# ButtonLatencyTester2.net
KiCad netlist of a schematic drawn in EAGLE
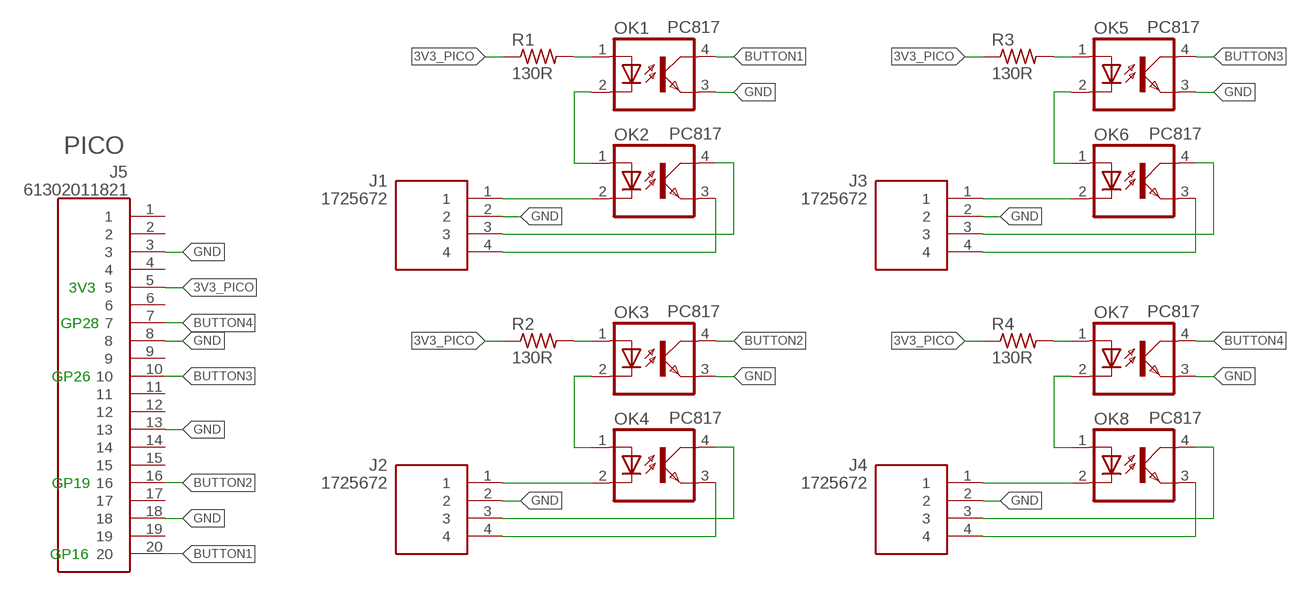
[diagram p0: schematic, sheet 1]

(export (version "E")
  (design (tool "Eeschema 10.0.6"))
  (components
    (comp (ref "J1")
      (value "1725672")
      (footprint "eagle-import:1725672-4-2.54")
      (fields (field (name "MOUSER_PART_NUMBER") "651-1725672"))
      (libsource (lib "eagle-import") (part "1725672"))
    )
    (comp (ref "J2")
      (value "1725672")
      (footprint "eagle-import:1725672-4-2.54")
      (fields (field (name "MOUSER_PART_NUMBER") "651-1725672"))
      (libsource (lib "eagle-import") (part "1725672"))
    )
    (comp (ref "J3")
      (value "1725672")
      (footprint "eagle-import:1725672-4-2.54")
      (fields (field (name "MOUSER_PART_NUMBER") "651-1725672"))
      (libsource (lib "eagle-import") (part "1725672"))
    )
    (comp (ref "J4")
      (value "1725672")
      (footprint "eagle-import:1725672-4-2.54")
      (fields (field (name "MOUSER_PART_NUMBER") "651-1725672"))
      (libsource (lib "eagle-import") (part "1725672"))
    )
    (comp (ref "J5")
      (value "61302011821")
      (footprint "eagle-import:RHDR20W60P0X254_1X20_5130X250X")
      (fields (field (name "MOUSER_PART_NUMBER") "710-61302011821"))
      (libsource (lib "eagle-import") (part "61302011821"))
    )
    (comp (ref "OK1")
      (value "PC817")
      (footprint "eagle-import:DIL04")
      (fields (field (name "MPN") "PC817X4J000F"))
      (libsource (lib "eagle-import") (part "PC817"))
    )
    (comp (ref "OK2")
      (value "PC817")
      (footprint "eagle-import:DIL04")
      (fields (field (name "MPN") "PC817X4J000F"))
      (libsource (lib "eagle-import") (part "PC817"))
    )
    (comp (ref "OK3")
      (value "PC817")
      (footprint "eagle-import:DIL04")
      (fields (field (name "MPN") "PC817X4J000F"))
      (libsource (lib "eagle-import") (part "PC817"))
    )
    (comp (ref "OK4")
      (value "PC817")
      (footprint "eagle-import:DIL04")
      (fields (field (name "MPN") "PC817X4J000F"))
      (libsource (lib "eagle-import") (part "PC817"))
    )
    (comp (ref "OK5")
      (value "PC817")
      (footprint "eagle-import:DIL04")
      (fields (field (name "MPN") "PC817X4J000F"))
      (libsource (lib "eagle-import") (part "PC817"))
    )
    (comp (ref "OK6")
      (value "PC817")
      (footprint "eagle-import:DIL04")
      (fields (field (name "MPN") "PC817X4J000F"))
      (libsource (lib "eagle-import") (part "PC817"))
    )
    (comp (ref "OK7")
      (value "PC817")
      (footprint "eagle-import:DIL04")
      (fields (field (name "MPN") "PC817X4J000F"))
      (libsource (lib "eagle-import") (part "PC817"))
    )
    (comp (ref "OK8")
      (value "PC817")
      (footprint "eagle-import:DIL04")
      (fields (field (name "MPN") "PC817X4J000F"))
      (libsource (lib "eagle-import") (part "PC817"))
    )
    (comp (ref "R1")
      (value "130R")
      (footprint "eagle-import:0204_7")
      (libsource (lib "eagle-import") (part "R-US_0204/7"))
    )
    (comp (ref "R2")
      (value "130R")
      (footprint "eagle-import:0204_7")
      (libsource (lib "eagle-import") (part "R-US_0204/7"))
    )
    (comp (ref "R3")
      (value "130R")
      (footprint "eagle-import:0204_7")
      (libsource (lib "eagle-import") (part "R-US_0204/7"))
    )
    (comp (ref "R4")
      (value "130R")
      (footprint "eagle-import:0204_7")
      (libsource (lib "eagle-import") (part "R-US_0204/7"))
    )
  )
  (nets
    (net (code "1") (name "3V3_PICO") (class "Default")
      (node (ref "J5") (pin "5") (pinfunction "5_5") (pintype "bidirectional"))
      (node (ref "R1") (pin "1") (pinfunction "1_1") (pintype "passive"))
      (node (ref "R2") (pin "1") (pinfunction "1_1") (pintype "passive"))
      (node (ref "R3") (pin "1") (pinfunction "1_1") (pintype "passive"))
      (node (ref "R4") (pin "1") (pinfunction "1_1") (pintype "passive"))
    )
    (net (code "2") (name "BUTTON1") (class "Default")
      (node (ref "J5") (pin "20") (pinfunction "20_20") (pintype "bidirectional"))
      (node (ref "OK1") (pin "4") (pinfunction "COL_4") (pintype "passive"))
    )
    (net (code "3") (name "BUTTON2") (class "Default")
      (node (ref "J5") (pin "16") (pinfunction "16_16") (pintype "bidirectional"))
      (node (ref "OK3") (pin "4") (pinfunction "COL_4") (pintype "passive"))
    )
    (net (code "4") (name "BUTTON3") (class "Default")
      (node (ref "J5") (pin "10") (pinfunction "10_10") (pintype "bidirectional"))
      (node (ref "OK5") (pin "4") (pinfunction "COL_4") (pintype "passive"))
    )
    (net (code "5") (name "BUTTON4") (class "Default")
      (node (ref "J5") (pin "7") (pinfunction "7_7") (pintype "bidirectional"))
      (node (ref "OK7") (pin "4") (pinfunction "COL_4") (pintype "passive"))
    )
    (net (code "6") (name "GND") (class "Default")
      (node (ref "J1") (pin "2") (pinfunction "2_2") (pintype "bidirectional"))
      (node (ref "J2") (pin "2") (pinfunction "2_2") (pintype "bidirectional"))
      (node (ref "J3") (pin "2") (pinfunction "2_2") (pintype "bidirectional"))
      (node (ref "J4") (pin "2") (pinfunction "2_2") (pintype "bidirectional"))
      (node (ref "J5") (pin "13") (pinfunction "13_13") (pintype "bidirectional"))
      (node (ref "J5") (pin "18") (pinfunction "18_18") (pintype "bidirectional"))
      (node (ref "J5") (pin "3") (pinfunction "3_3") (pintype "bidirectional"))
      (node (ref "J5") (pin "8") (pinfunction "8_8") (pintype "bidirectional"))
      (node (ref "OK1") (pin "3") (pinfunction "EMIT_3") (pintype "passive"))
      (node (ref "OK3") (pin "3") (pinfunction "EMIT_3") (pintype "passive"))
      (node (ref "OK5") (pin "3") (pinfunction "EMIT_3") (pintype "passive"))
      (node (ref "OK7") (pin "3") (pinfunction "EMIT_3") (pintype "passive"))
    )
    (net (code "7") (name "Net-(OK1-A)") (class "Default")
      (node (ref "OK1") (pin "1") (pinfunction "A_1") (pintype "passive"))
      (node (ref "R1") (pin "2") (pinfunction "2_2") (pintype "passive"))
    )
    (net (code "8") (name "Net-(OK1-C)") (class "Default")
      (node (ref "OK1") (pin "2") (pinfunction "C_2") (pintype "passive"))
      (node (ref "OK2") (pin "1") (pinfunction "A_1") (pintype "passive"))
    )
    (net (code "9") (name "Net-(OK2-C)") (class "Default")
      (node (ref "J1") (pin "1") (pinfunction "1_1") (pintype "bidirectional"))
      (node (ref "OK2") (pin "2") (pinfunction "C_2") (pintype "passive"))
    )
    (net (code "10") (name "Net-(OK2-COL)") (class "Default")
      (node (ref "J1") (pin "3") (pinfunction "3_3") (pintype "bidirectional"))
      (node (ref "OK2") (pin "4") (pinfunction "COL_4") (pintype "passive"))
    )
    (net (code "11") (name "Net-(OK2-EMIT)") (class "Default")
      (node (ref "J1") (pin "4") (pinfunction "4_4") (pintype "bidirectional"))
      (node (ref "OK2") (pin "3") (pinfunction "EMIT_3") (pintype "passive"))
    )
    (net (code "12") (name "Net-(OK3-A)") (class "Default")
      (node (ref "OK3") (pin "1") (pinfunction "A_1") (pintype "passive"))
      (node (ref "R2") (pin "2") (pinfunction "2_2") (pintype "passive"))
    )
    (net (code "13") (name "Net-(OK3-C)") (class "Default")
      (node (ref "OK3") (pin "2") (pinfunction "C_2") (pintype "passive"))
      (node (ref "OK4") (pin "1") (pinfunction "A_1") (pintype "passive"))
    )
    (net (code "14") (name "Net-(OK4-C)") (class "Default")
      (node (ref "J2") (pin "1") (pinfunction "1_1") (pintype "bidirectional"))
      (node (ref "OK4") (pin "2") (pinfunction "C_2") (pintype "passive"))
    )
    (net (code "15") (name "Net-(OK4-COL)") (class "Default")
      (node (ref "J2") (pin "3") (pinfunction "3_3") (pintype "bidirectional"))
      (node (ref "OK4") (pin "4") (pinfunction "COL_4") (pintype "passive"))
    )
    (net (code "16") (name "Net-(OK4-EMIT)") (class "Default")
      (node (ref "J2") (pin "4") (pinfunction "4_4") (pintype "bidirectional"))
      (node (ref "OK4") (pin "3") (pinfunction "EMIT_3") (pintype "passive"))
    )
    (net (code "17") (name "Net-(OK5-A)") (class "Default")
      (node (ref "OK5") (pin "1") (pinfunction "A_1") (pintype "passive"))
      (node (ref "R3") (pin "2") (pinfunction "2_2") (pintype "passive"))
    )
    (net (code "18") (name "Net-(OK5-C)") (class "Default")
      (node (ref "OK5") (pin "2") (pinfunction "C_2") (pintype "passive"))
      (node (ref "OK6") (pin "1") (pinfunction "A_1") (pintype "passive"))
    )
    (net (code "19") (name "Net-(OK6-C)") (class "Default")
      (node (ref "J3") (pin "1") (pinfunction "1_1") (pintype "bidirectional"))
      (node (ref "OK6") (pin "2") (pinfunction "C_2") (pintype "passive"))
    )
    (net (code "20") (name "Net-(OK6-COL)") (class "Default")
      (node (ref "J3") (pin "3") (pinfunction "3_3") (pintype "bidirectional"))
      (node (ref "OK6") (pin "4") (pinfunction "COL_4") (pintype "passive"))
    )
    (net (code "21") (name "Net-(OK6-EMIT)") (class "Default")
      (node (ref "J3") (pin "4") (pinfunction "4_4") (pintype "bidirectional"))
      (node (ref "OK6") (pin "3") (pinfunction "EMIT_3") (pintype "passive"))
    )
    (net (code "22") (name "Net-(OK7-A)") (class "Default")
      (node (ref "OK7") (pin "1") (pinfunction "A_1") (pintype "passive"))
      (node (ref "R4") (pin "2") (pinfunction "2_2") (pintype "passive"))
    )
    (net (code "23") (name "Net-(OK7-C)") (class "Default")
      (node (ref "OK7") (pin "2") (pinfunction "C_2") (pintype "passive"))
      (node (ref "OK8") (pin "1") (pinfunction "A_1") (pintype "passive"))
    )
    (net (code "24") (name "Net-(OK8-C)") (class "Default")
      (node (ref "J4") (pin "1") (pinfunction "1_1") (pintype "bidirectional"))
      (node (ref "OK8") (pin "2") (pinfunction "C_2") (pintype "passive"))
    )
    (net (code "25") (name "Net-(OK8-COL)") (class "Default")
      (node (ref "J4") (pin "3") (pinfunction "3_3") (pintype "bidirectional"))
      (node (ref "OK8") (pin "4") (pinfunction "COL_4") (pintype "passive"))
    )
    (net (code "26") (name "Net-(OK8-EMIT)") (class "Default")
      (node (ref "J4") (pin "4") (pinfunction "4_4") (pintype "bidirectional"))
      (node (ref "OK8") (pin "3") (pinfunction "EMIT_3") (pintype "passive"))
    )
    (net (code "27") (name "unconnected-(J5-Pad1)") (class "Default")
      (node (ref "J5") (pin "1") (pinfunction "1_1") (pintype "bidirectional"))
    )
    (net (code "28") (name "unconnected-(J5-Pad2)") (class "Default")
      (node (ref "J5") (pin "2") (pinfunction "2_2") (pintype "bidirectional"))
    )
    (net (code "29") (name "unconnected-(J5-Pad4)") (class "Default")
      (node (ref "J5") (pin "4") (pinfunction "4_4") (pintype "bidirectional"))
    )
    (net (code "30") (name "unconnected-(J5-Pad6)") (class "Default")
      (node (ref "J5") (pin "6") (pinfunction "6_6") (pintype "bidirectional"))
    )
    (net (code "31") (name "unconnected-(J5-Pad9)") (class "Default")
      (node (ref "J5") (pin "9") (pinfunction "9_9") (pintype "bidirectional"))
    )
    (net (code "32") (name "unconnected-(J5-Pad11)") (class "Default")
      (node (ref "J5") (pin "11") (pinfunction "11_11") (pintype "bidirectional"))
    )
    (net (code "33") (name "unconnected-(J5-Pad12)") (class "Default")
      (node (ref "J5") (pin "12") (pinfunction "12_12") (pintype "bidirectional"))
    )
    (net (code "34") (name "unconnected-(J5-Pad14)") (class "Default")
      (node (ref "J5") (pin "14") (pinfunction "14_14") (pintype "bidirectional"))
    )
    (net (code "35") (name "unconnected-(J5-Pad15)") (class "Default")
      (node (ref "J5") (pin "15") (pinfunction "15_15") (pintype "bidirectional"))
    )
    (net (code "36") (name "unconnected-(J5-Pad17)") (class "Default")
      (node (ref "J5") (pin "17") (pinfunction "17_17") (pintype "bidirectional"))
    )
    (net (code "37") (name "unconnected-(J5-Pad19)") (class "Default")
      (node (ref "J5") (pin "19") (pinfunction "19_19") (pintype "bidirectional"))
    )
  )
)
